# POWER_OSC_BOOT.net
KiCad netlist of a schematic drawn in Altium Designer
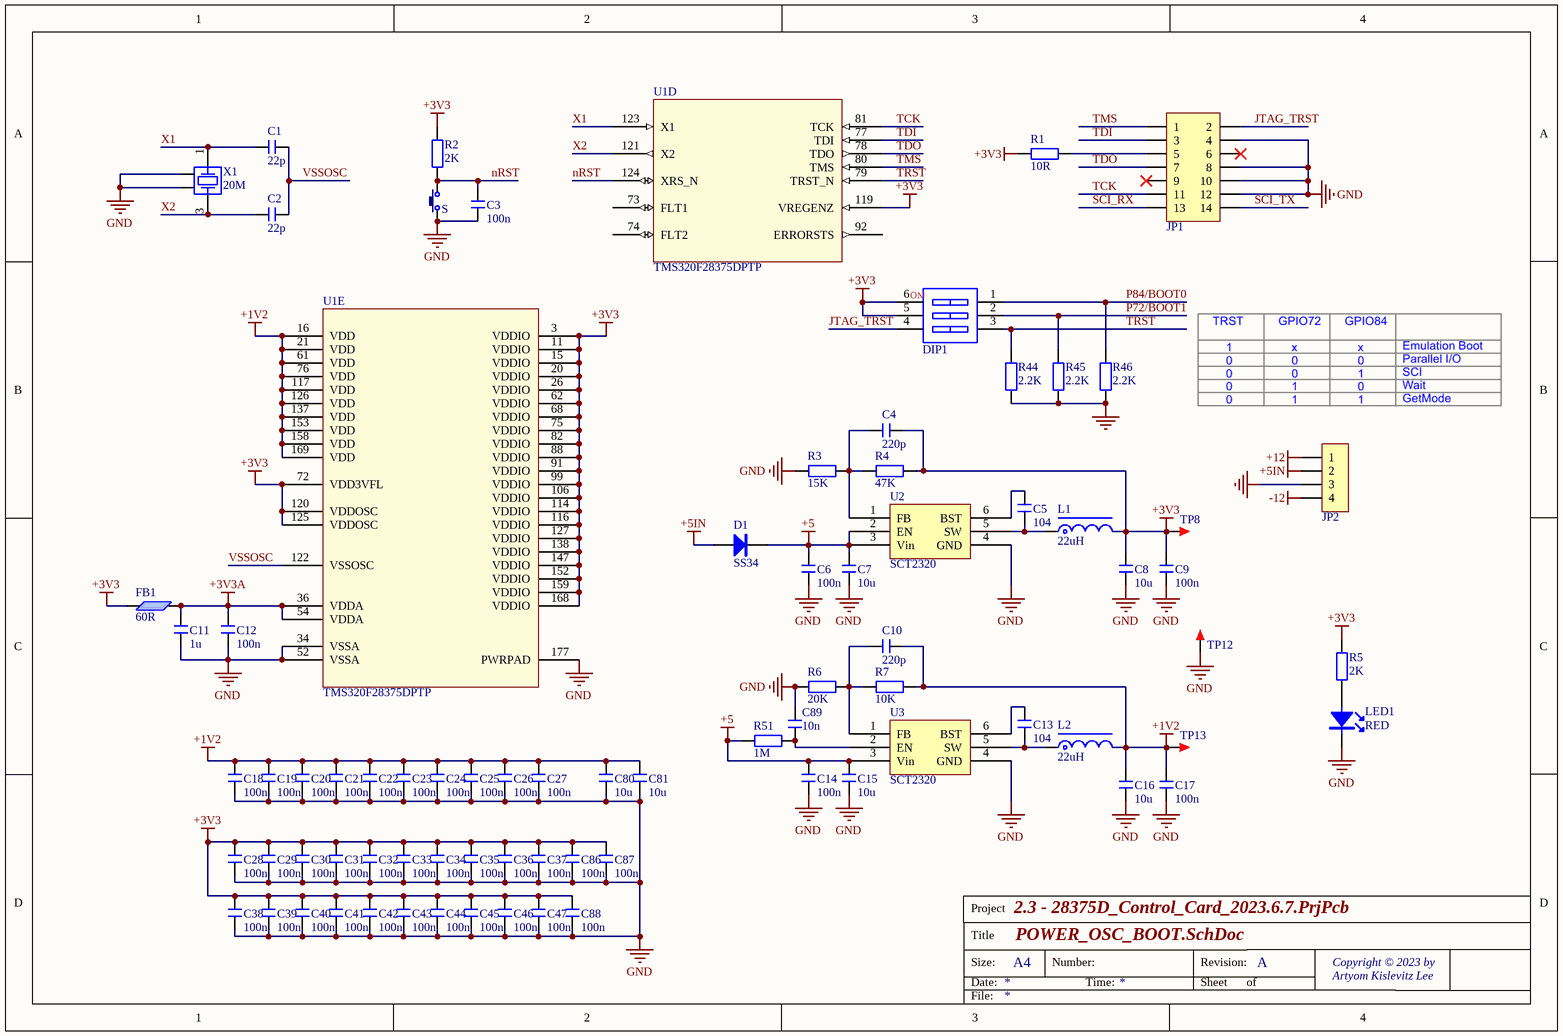
[diagram p0: POWER_OSC_BOOT.SchDoc]

(export (version "E")
  (design (tool "Eeschema 10.0.6"))
  (components
    (comp (ref "C1")
      (value "22p")
      (footprint "C 0805_L")
      (description "贴片电容")
      (libsource (lib "01 - 电容-电阻-电感") (part "C"))
    )
    (comp (ref "C2")
      (value "22p")
      (footprint "C 0805_L")
      (description "贴片电容")
      (libsource (lib "01 - 电容-电阻-电感") (part "C"))
    )
    (comp (ref "C3")
      (value "100n")
      (footprint "C 0805_L")
      (description "贴片电容")
      (libsource (lib "01 - 电容-电阻-电感") (part "C"))
    )
    (comp (ref "C4")
      (value "220p")
      (footprint "C 0805_L")
      (description "贴片电容")
      (libsource (lib "01 - 电容-电阻-电感") (part "C"))
    )
    (comp (ref "C5")
      (value "104")
      (footprint "C 0805_L")
      (description "贴片电容")
      (libsource (lib "01 - 电容-电阻-电感") (part "C"))
    )
    (comp (ref "C6")
      (value "100n")
      (footprint "C 0805_L")
      (description "贴片电容")
      (libsource (lib "01 - 电容-电阻-电感") (part "C"))
    )
    (comp (ref "C7")
      (value "10u")
      (footprint "C 1210_L")
      (description "贴片电容")
      (libsource (lib "01 - 电容-电阻-电感") (part "C"))
    )
    (comp (ref "C8")
      (value "10u")
      (footprint "C 1210_L")
      (description "贴片电容")
      (libsource (lib "01 - 电容-电阻-电感") (part "C"))
    )
    (comp (ref "C9")
      (value "100n")
      (footprint "C 0805_L")
      (description "贴片电容")
      (libsource (lib "01 - 电容-电阻-电感") (part "C"))
    )
    (comp (ref "C10")
      (value "220p")
      (footprint "C 0805_L")
      (description "贴片电容")
      (libsource (lib "01 - 电容-电阻-电感") (part "C"))
    )
    (comp (ref "C11")
      (value "1u")
      (footprint "C 0805_L")
      (description "贴片电容")
      (libsource (lib "01 - 电容-电阻-电感") (part "C"))
    )
    (comp (ref "C12")
      (value "100n")
      (footprint "C 0805_L")
      (description "贴片电容")
      (libsource (lib "01 - 电容-电阻-电感") (part "C"))
    )
    (comp (ref "C13")
      (value "104")
      (footprint "C 0805_L")
      (description "贴片电容")
      (libsource (lib "01 - 电容-电阻-电感") (part "C"))
    )
    (comp (ref "C14")
      (value "100n")
      (footprint "C 0805_L")
      (description "贴片电容")
      (libsource (lib "01 - 电容-电阻-电感") (part "C"))
    )
    (comp (ref "C15")
      (value "10u")
      (footprint "C 1210_L")
      (description "贴片电容")
      (libsource (lib "01 - 电容-电阻-电感") (part "C"))
    )
    (comp (ref "C16")
      (value "10u")
      (footprint "C 1210_L")
      (description "贴片电容")
      (libsource (lib "01 - 电容-电阻-电感") (part "C"))
    )
    (comp (ref "C17")
      (value "100n")
      (footprint "C 0805_L")
      (description "贴片电容")
      (libsource (lib "01 - 电容-电阻-电感") (part "C"))
    )
    (comp (ref "C18")
      (value "100n")
      (footprint "C 0603_L")
      (description "贴片电容")
      (libsource (lib "01 - 电容-电阻-电感") (part "C"))
    )
    (comp (ref "C19")
      (value "100n")
      (footprint "C 0603_L")
      (description "贴片电容")
      (libsource (lib "01 - 电容-电阻-电感") (part "C"))
    )
    (comp (ref "C20")
      (value "100n")
      (footprint "C 0603_L")
      (description "贴片电容")
      (libsource (lib "01 - 电容-电阻-电感") (part "C"))
    )
    (comp (ref "C21")
      (value "100n")
      (footprint "C 0603_L")
      (description "贴片电容")
      (libsource (lib "01 - 电容-电阻-电感") (part "C"))
    )
    (comp (ref "C22")
      (value "100n")
      (footprint "C 0603_L")
      (description "贴片电容")
      (libsource (lib "01 - 电容-电阻-电感") (part "C"))
    )
    (comp (ref "C23")
      (value "100n")
      (footprint "C 0603_L")
      (description "贴片电容")
      (libsource (lib "01 - 电容-电阻-电感") (part "C"))
    )
    (comp (ref "C24")
      (value "100n")
      (footprint "C 0603_L")
      (description "贴片电容")
      (libsource (lib "01 - 电容-电阻-电感") (part "C"))
    )
    (comp (ref "C25")
      (value "100n")
      (footprint "C 0603_L")
      (description "贴片电容")
      (libsource (lib "01 - 电容-电阻-电感") (part "C"))
    )
    (comp (ref "C26")
      (value "100n")
      (footprint "C 0603_L")
      (description "贴片电容")
      (libsource (lib "01 - 电容-电阻-电感") (part "C"))
    )
    (comp (ref "C27")
      (value "100n")
      (footprint "C 0603_L")
      (description "贴片电容")
      (libsource (lib "01 - 电容-电阻-电感") (part "C"))
    )
    (comp (ref "C28")
      (value "100n")
      (footprint "C 0603_L")
      (description "贴片电容")
      (libsource (lib "01 - 电容-电阻-电感") (part "C"))
    )
    (comp (ref "C29")
      (value "100n")
      (footprint "C 0603_L")
      (description "贴片电容")
      (libsource (lib "01 - 电容-电阻-电感") (part "C"))
    )
    (comp (ref "C30")
      (value "100n")
      (footprint "C 0603_L")
      (description "贴片电容")
      (libsource (lib "01 - 电容-电阻-电感") (part "C"))
    )
    (comp (ref "C31")
      (value "100n")
      (footprint "C 0603_L")
      (description "贴片电容")
      (libsource (lib "01 - 电容-电阻-电感") (part "C"))
    )
    (comp (ref "C32")
      (value "100n")
      (footprint "C 0603_L")
      (description "贴片电容")
      (libsource (lib "01 - 电容-电阻-电感") (part "C"))
    )
    (comp (ref "C33")
      (value "100n")
      (footprint "C 0603_L")
      (description "贴片电容")
      (libsource (lib "01 - 电容-电阻-电感") (part "C"))
    )
    (comp (ref "C34")
      (value "100n")
      (footprint "C 0603_L")
      (description "贴片电容")
      (libsource (lib "01 - 电容-电阻-电感") (part "C"))
    )
    (comp (ref "C35")
      (value "100n")
      (footprint "C 0603_L")
      (description "贴片电容")
      (libsource (lib "01 - 电容-电阻-电感") (part "C"))
    )
    (comp (ref "C36")
      (value "100n")
      (footprint "C 0603_L")
      (description "贴片电容")
      (libsource (lib "01 - 电容-电阻-电感") (part "C"))
    )
    (comp (ref "C37")
      (value "100n")
      (footprint "C 0603_L")
      (description "贴片电容")
      (libsource (lib "01 - 电容-电阻-电感") (part "C"))
    )
    (comp (ref "C38")
      (value "100n")
      (footprint "C 0603_L")
      (description "贴片电容")
      (libsource (lib "01 - 电容-电阻-电感") (part "C"))
    )
    (comp (ref "C39")
      (value "100n")
      (footprint "C 0603_L")
      (description "贴片电容")
      (libsource (lib "01 - 电容-电阻-电感") (part "C"))
    )
    (comp (ref "C40")
      (value "100n")
      (footprint "C 0603_L")
      (description "贴片电容")
      (libsource (lib "01 - 电容-电阻-电感") (part "C"))
    )
    (comp (ref "C41")
      (value "100n")
      (footprint "C 0603_L")
      (description "贴片电容")
      (libsource (lib "01 - 电容-电阻-电感") (part "C"))
    )
    (comp (ref "C42")
      (value "100n")
      (footprint "C 0603_L")
      (description "贴片电容")
      (libsource (lib "01 - 电容-电阻-电感") (part "C"))
    )
    (comp (ref "C43")
      (value "100n")
      (footprint "C 0603_L")
      (description "贴片电容")
      (libsource (lib "01 - 电容-电阻-电感") (part "C"))
    )
    (comp (ref "C44")
      (value "100n")
      (footprint "C 0603_L")
      (description "贴片电容")
      (libsource (lib "01 - 电容-电阻-电感") (part "C"))
    )
    (comp (ref "C45")
      (value "100n")
      (footprint "C 0603_L")
      (description "贴片电容")
      (libsource (lib "01 - 电容-电阻-电感") (part "C"))
    )
    (comp (ref "C46")
      (value "100n")
      (footprint "C 0603_L")
      (description "贴片电容")
      (libsource (lib "01 - 电容-电阻-电感") (part "C"))
    )
    (comp (ref "C47")
      (value "100n")
      (footprint "C 0603_L")
      (description "贴片电容")
      (libsource (lib "01 - 电容-电阻-电感") (part "C"))
    )
    (comp (ref "C80")
      (value "10u")
      (footprint "C 0805_L")
      (description "贴片电容")
      (libsource (lib "01 - 电容-电阻-电感") (part "C"))
    )
    (comp (ref "C81")
      (value "10u")
      (footprint "C 0805_L")
      (description "贴片电容")
      (libsource (lib "01 - 电容-电阻-电感") (part "C"))
    )
    (comp (ref "C86")
      (value "100n")
      (footprint "C 0603_L")
      (description "贴片电容")
      (libsource (lib "01 - 电容-电阻-电感") (part "C"))
    )
    (comp (ref "C87")
      (value "100n")
      (footprint "C 0603_L")
      (description "贴片电容")
      (libsource (lib "01 - 电容-电阻-电感") (part "C"))
    )
    (comp (ref "C88")
      (value "100n")
      (footprint "C 0603_L")
      (description "贴片电容")
      (libsource (lib "01 - 电容-电阻-电感") (part "C"))
    )
    (comp (ref "C89")
      (value "10n")
      (footprint "C 0805_L")
      (description "贴片电容")
      (libsource (lib "01 - 电容-电阻-电感") (part "C"))
    )
    (comp (ref "D1")
      (value "SS34")
      (footprint "SMA")
      (description "整流二极管")
      (libsource (lib "02 - 二极管(LED)-三极管-整流桥") (part "1N4007"))
    )
    (comp (ref "DIP1")
      (value "SW-3P")
      (footprint "CSW1.27 SMD-3P")
      (description "3路编码开关")
      (libsource (lib "03 - 按键-开关-晶振-蜂鸣器") (part "SW-3P"))
    )
    (comp (ref "FB1")
      (value "60R")
      (footprint "R 0805_L")
      (description "磁珠")
      (libsource (lib "01 - 电容-电阻-电感") (part "FB"))
    )
    (comp (ref "JP1")
      (value "Header 2X7")
      (footprint "IDC2.54-LI-2x7P")
      (description "7*2P接插件")
      (libsource (lib "18 - 接插件-脚距2.54mm (100mil) ") (part "Header 7X2"))
    )
    (comp (ref "JP2")
      (value "HDR-1X4")
      (footprint "KF2510-LI-4P")
      (description "4P接插件")
      (libsource (lib "18 - 接插件-脚距2.54mm (100mil) ") (part "Header 4"))
    )
    (comp (ref "L1")
      (value "22uH")
      (footprint "CDRH74")
      (description "功率屏蔽电感")
      (libsource (lib "01 - 电容-电阻-电感") (part "L-CDRH"))
    )
    (comp (ref "L2")
      (value "22uH")
      (footprint "CDRH74")
      (description "功率屏蔽电感")
      (libsource (lib "01 - 电容-电阻-电感") (part "L-CDRH"))
    )
    (comp (ref "LED1")
      (value "RED")
      (footprint "LED 0805R")
      (description "贴片LED")
      (libsource (lib "02 - 二极管(LED)-三极管-整流桥") (part "LED-SMD"))
    )
    (comp (ref "R1")
      (value "10R")
      (footprint "R 0805_L")
      (description "贴片电阻")
      (libsource (lib "01 - 电容-电阻-电感") (part "R"))
    )
    (comp (ref "R2")
      (value "2K")
      (footprint "R 0805_L")
      (description "贴片电阻")
      (libsource (lib "01 - 电容-电阻-电感") (part "R"))
    )
    (comp (ref "R3")
      (value "15K")
      (footprint "R 0805_L")
      (description "贴片电阻")
      (libsource (lib "01 - 电容-电阻-电感") (part "R"))
    )
    (comp (ref "R4")
      (value "47K")
      (footprint "R 0805_L")
      (description "贴片电阻")
      (libsource (lib "01 - 电容-电阻-电感") (part "R"))
    )
    (comp (ref "R5")
      (value "2K")
      (footprint "R 0805_L")
      (description "贴片电阻")
      (libsource (lib "01 - 电容-电阻-电感") (part "R"))
    )
    (comp (ref "R6")
      (value "20K")
      (footprint "R 0805_L")
      (description "贴片电阻")
      (libsource (lib "01 - 电容-电阻-电感") (part "R"))
    )
    (comp (ref "R7")
      (value "10K")
      (footprint "R 0805_L")
      (description "贴片电阻")
      (libsource (lib "01 - 电容-电阻-电感") (part "R"))
    )
    (comp (ref "R44")
      (value "2.2K")
      (footprint "R 0805_L")
      (description "贴片电阻")
      (libsource (lib "01 - 电容-电阻-电感") (part "R"))
    )
    (comp (ref "R45")
      (value "2.2K")
      (footprint "R 0805_L")
      (description "贴片电阻")
      (libsource (lib "01 - 电容-电阻-电感") (part "R"))
    )
    (comp (ref "R46")
      (value "2.2K")
      (footprint "R 0805_L")
      (description "贴片电阻")
      (libsource (lib "01 - 电容-电阻-电感") (part "R"))
    )
    (comp (ref "R51")
      (value "1M")
      (footprint "R 0805_L")
      (description "贴片电阻")
      (libsource (lib "01 - 电容-电阻-电感") (part "R"))
    )
    (comp (ref "S")
      (value "3x6x5")
      (footprint "TSW DIP-3*6*4.3")
      (description "3x6轻触开关")
      (libsource (lib "03 - 按键-开关-晶振-蜂鸣器") (part "TSW 3x6"))
    )
    (comp (ref "TP8")
      (value "TEST")
      (footprint "TEST 1.6")
      (description "测试点")
      (libsource (lib "10 - 未分类元器件") (part "TEST"))
    )
    (comp (ref "TP12")
      (value "TEST")
      (footprint "TEST 1.6")
      (description "测试点")
      (libsource (lib "10 - 未分类元器件") (part "TEST"))
    )
    (comp (ref "TP13")
      (value "TEST")
      (footprint "TEST 1.6")
      (description "测试点")
      (libsource (lib "10 - 未分类元器件") (part "TEST"))
    )
    (comp (ref "U1")
      (value "TMS320F28375DPTP")
      (footprint "LQFP176-E 24x24_N")
      (description "DSP 176")
      (fields
        (field (name "PARTNUMBER") "TMS320F28377DPTP")
        (field (name "MANUFACTURER") "Texas Instruments")
      )
      (libsource (lib "39 - 其他芯片类") (part "TMS320F28377DPTP"))
    )
    (comp (ref "U2") (value "SCT2320") (footprint "SOT23-6") (libsource (lib "Schlib1") (part "SCT2330")))
    (comp (ref "U3") (value "SCT2320") (footprint "SOT23-6") (libsource (lib "Schlib1") (part "SCT2330")))
    (comp (ref "X1")
      (value "20M")
      (footprint "OSC 3225-4P")
      (description "4脚无源晶振")
      (libsource (lib "03 - 按键-开关-晶振-蜂鸣器") (part "XTAL-4P"))
    )
  )
  (nets
    (net (code "1") (name "+1V2") (class "Default")
      (node (ref "C10") (pin "2") (pinfunction "2_2") (pintype "passive"))
      (node (ref "C16") (pin "2") (pinfunction "2_2") (pintype "passive"))
      (node (ref "C17") (pin "2") (pinfunction "2_2") (pintype "passive"))
      (node (ref "C18") (pin "2") (pinfunction "2_2") (pintype "passive"))
      (node (ref "C19") (pin "2") (pinfunction "2_2") (pintype "passive"))
      (node (ref "C20") (pin "2") (pinfunction "2_2") (pintype "passive"))
      (node (ref "C21") (pin "2") (pinfunction "2_2") (pintype "passive"))
      (node (ref "C22") (pin "2") (pinfunction "2_2") (pintype "passive"))
      (node (ref "C23") (pin "2") (pinfunction "2_2") (pintype "passive"))
      (node (ref "C24") (pin "2") (pinfunction "2_2") (pintype "passive"))
      (node (ref "C25") (pin "2") (pinfunction "2_2") (pintype "passive"))
      (node (ref "C26") (pin "2") (pinfunction "2_2") (pintype "passive"))
      (node (ref "C27") (pin "2") (pinfunction "2_2") (pintype "passive"))
      (node (ref "C80") (pin "2") (pinfunction "2_2") (pintype "passive"))
      (node (ref "C81") (pin "2") (pinfunction "2_2") (pintype "passive"))
      (node (ref "L2") (pin "2") (pinfunction "2_2") (pintype "passive"))
      (node (ref "R7") (pin "2") (pinfunction "2_2") (pintype "passive"))
      (node (ref "TP13") (pin "1") (pinfunction "1_1") (pintype "passive"))
      (node (ref "U1") (pin "117") (pinfunction "VDD_117") (pintype "power_in"))
      (node (ref "U1") (pin "126") (pinfunction "VDD_126") (pintype "power_in"))
      (node (ref "U1") (pin "137") (pinfunction "VDD_137") (pintype "power_in"))
      (node (ref "U1") (pin "153") (pinfunction "VDD_153") (pintype "power_in"))
      (node (ref "U1") (pin "158") (pinfunction "VDD_158") (pintype "power_in"))
      (node (ref "U1") (pin "16") (pinfunction "VDD_16") (pintype "power_in"))
      (node (ref "U1") (pin "169") (pinfunction "VDD_169") (pintype "power_in"))
      (node (ref "U1") (pin "21") (pinfunction "VDD_21") (pintype "power_in"))
      (node (ref "U1") (pin "61") (pinfunction "VDD_61") (pintype "power_in"))
      (node (ref "U1") (pin "76") (pinfunction "VDD_76") (pintype "power_in"))
    )
    (net (code "2") (name "+3V3") (class "Default")
      (node (ref "C28") (pin "2") (pinfunction "2_2") (pintype "passive"))
      (node (ref "C29") (pin "2") (pinfunction "2_2") (pintype "passive"))
      (node (ref "C30") (pin "2") (pinfunction "2_2") (pintype "passive"))
      (node (ref "C31") (pin "2") (pinfunction "2_2") (pintype "passive"))
      (node (ref "C32") (pin "2") (pinfunction "2_2") (pintype "passive"))
      (node (ref "C33") (pin "2") (pinfunction "2_2") (pintype "passive"))
      (node (ref "C34") (pin "2") (pinfunction "2_2") (pintype "passive"))
      (node (ref "C35") (pin "2") (pinfunction "2_2") (pintype "passive"))
      (node (ref "C36") (pin "2") (pinfunction "2_2") (pintype "passive"))
      (node (ref "C37") (pin "2") (pinfunction "2_2") (pintype "passive"))
      (node (ref "C38") (pin "2") (pinfunction "2_2") (pintype "passive"))
      (node (ref "C39") (pin "2") (pinfunction "2_2") (pintype "passive"))
      (node (ref "C4") (pin "2") (pinfunction "2_2") (pintype "passive"))
      (node (ref "C40") (pin "2") (pinfunction "2_2") (pintype "passive"))
      (node (ref "C41") (pin "2") (pinfunction "2_2") (pintype "passive"))
      (node (ref "C42") (pin "2") (pinfunction "2_2") (pintype "passive"))
      (node (ref "C43") (pin "2") (pinfunction "2_2") (pintype "passive"))
      (node (ref "C44") (pin "2") (pinfunction "2_2") (pintype "passive"))
      (node (ref "C45") (pin "2") (pinfunction "2_2") (pintype "passive"))
      (node (ref "C46") (pin "2") (pinfunction "2_2") (pintype "passive"))
      (node (ref "C47") (pin "2") (pinfunction "2_2") (pintype "passive"))
      (node (ref "C8") (pin "2") (pinfunction "2_2") (pintype "passive"))
      (node (ref "C86") (pin "2") (pinfunction "2_2") (pintype "passive"))
      (node (ref "C87") (pin "2") (pinfunction "2_2") (pintype "passive"))
      (node (ref "C88") (pin "2") (pinfunction "2_2") (pintype "passive"))
      (node (ref "C9") (pin "2") (pinfunction "2_2") (pintype "passive"))
      (node (ref "DIP1") (pin "5") (pinfunction "5_5") (pintype "passive"))
      (node (ref "DIP1") (pin "6") (pinfunction "6_6") (pintype "passive"))
      (node (ref "FB1") (pin "1") (pinfunction "1_1") (pintype "passive"))
      (node (ref "L1") (pin "2") (pinfunction "2_2") (pintype "passive"))
      (node (ref "R1") (pin "2") (pinfunction "2_2") (pintype "passive"))
      (node (ref "R2") (pin "2") (pinfunction "2_2") (pintype "passive"))
      (node (ref "R4") (pin "2") (pinfunction "2_2") (pintype "passive"))
      (node (ref "R5") (pin "2") (pinfunction "2_2") (pintype "passive"))
      (node (ref "TP8") (pin "1") (pinfunction "1_1") (pintype "passive"))
      (node (ref "U1") (pin "106") (pinfunction "VDDIO_106") (pintype "power_in"))
      (node (ref "U1") (pin "11") (pinfunction "VDDIO_11") (pintype "power_in"))
      (node (ref "U1") (pin "114") (pinfunction "VDDIO_114") (pintype "power_in"))
      (node (ref "U1") (pin "116") (pinfunction "VDDIO_116") (pintype "power_in"))
      (node (ref "U1") (pin "119") (pinfunction "VREGENZ_119") (pintype "input"))
      (node (ref "U1") (pin "120") (pinfunction "VDDOSC_120") (pintype "power_in"))
      (node (ref "U1") (pin "125") (pinfunction "VDDOSC_125") (pintype "power_in"))
      (node (ref "U1") (pin "127") (pinfunction "VDDIO_127") (pintype "power_in"))
      (node (ref "U1") (pin "138") (pinfunction "VDDIO_138") (pintype "power_in"))
      (node (ref "U1") (pin "147") (pinfunction "VDDIO_147") (pintype "power_in"))
      (node (ref "U1") (pin "15") (pinfunction "VDDIO_15") (pintype "power_in"))
      (node (ref "U1") (pin "152") (pinfunction "VDDIO_152") (pintype "power_in"))
      (node (ref "U1") (pin "159") (pinfunction "VDDIO_159") (pintype "power_in"))
      (node (ref "U1") (pin "168") (pinfunction "VDDIO_168") (pintype "power_in"))
      (node (ref "U1") (pin "20") (pinfunction "VDDIO_20") (pintype "power_in"))
      (node (ref "U1") (pin "26") (pinfunction "VDDIO_26") (pintype "power_in"))
      (node (ref "U1") (pin "3") (pinfunction "VDDIO_3") (pintype "power_in"))
      (node (ref "U1") (pin "62") (pinfunction "VDDIO_62") (pintype "power_in"))
      (node (ref "U1") (pin "68") (pinfunction "VDDIO_68") (pintype "power_in"))
      (node (ref "U1") (pin "72") (pinfunction "VDD3VFL_72") (pintype "power_in"))
      (node (ref "U1") (pin "75") (pinfunction "VDDIO_75") (pintype "power_in"))
      (node (ref "U1") (pin "82") (pinfunction "VDDIO_82") (pintype "power_in"))
      (node (ref "U1") (pin "88") (pinfunction "VDDIO_88") (pintype "power_in"))
      (node (ref "U1") (pin "91") (pinfunction "VDDIO_91") (pintype "power_in"))
      (node (ref "U1") (pin "99") (pinfunction "VDDIO_99") (pintype "power_in"))
    )
    (net (code "3") (name "+3V3A") (class "Default")
      (node (ref "C11") (pin "2") (pinfunction "2_2") (pintype "passive"))
      (node (ref "C12") (pin "2") (pinfunction "2_2") (pintype "passive"))
      (node (ref "FB1") (pin "2") (pinfunction "2_2") (pintype "passive"))
      (node (ref "U1") (pin "36") (pinfunction "VDDA_36") (pintype "power_in"))
      (node (ref "U1") (pin "54") (pinfunction "VDDA_54") (pintype "power_in"))
    )
    (net (code "4") (name "+5") (class "Default")
      (node (ref "C14") (pin "2") (pinfunction "2_2") (pintype "passive"))
      (node (ref "C15") (pin "2") (pinfunction "2_2") (pintype "passive"))
      (node (ref "C6") (pin "2") (pinfunction "2_2") (pintype "passive"))
      (node (ref "C7") (pin "2") (pinfunction "2_2") (pintype "passive"))
      (node (ref "D1") (pin "2") (pinfunction "K_2") (pintype "passive"))
      (node (ref "R51") (pin "1") (pinfunction "1_1") (pintype "passive"))
      (node (ref "U2") (pin "2") (pinfunction "EN_2") (pintype "passive"))
      (node (ref "U2") (pin "3") (pinfunction "Vin_3") (pintype "passive"))
      (node (ref "U3") (pin "3") (pinfunction "Vin_3") (pintype "passive"))
    )
    (net (code "5") (name "+5IN") (class "Default")
      (node (ref "D1") (pin "1") (pinfunction "A_1") (pintype "passive"))
      (node (ref "JP2") (pin "2") (pinfunction "2_2") (pintype "passive"))
    )
    (net (code "6") (name "+12") (class "Default")
      (node (ref "JP2") (pin "1") (pinfunction "1_1") (pintype "passive"))
    )
    (net (code "7") (name "-12") (class "Default")
      (node (ref "JP2") (pin "4") (pinfunction "4_4") (pintype "passive"))
    )
    (net (code "8") (name "/JTAG_TRST") (class "Default")
      (node (ref "DIP1") (pin "4") (pinfunction "4_4") (pintype "passive"))
      (node (ref "JP1") (pin "2") (pinfunction "2_2") (pintype "passive"))
    )
    (net (code "9") (name "/P72{slash}BOOT1") (class "Default")
      (node (ref "DIP1") (pin "2") (pinfunction "2_2") (pintype "passive"))
      (node (ref "R45") (pin "1") (pinfunction "1_1") (pintype "passive"))
    )
    (net (code "10") (name "/P84{slash}BOOT0") (class "Default")
      (node (ref "DIP1") (pin "1") (pinfunction "1_1") (pintype "passive"))
      (node (ref "R46") (pin "1") (pinfunction "1_1") (pintype "passive"))
    )
    (net (code "11") (name "/SCI_RX") (class "Default")
      (node (ref "JP1") (pin "13") (pinfunction "13_13") (pintype "passive"))
    )
    (net (code "12") (name "/SCI_TX") (class "Default")
      (node (ref "JP1") (pin "14") (pinfunction "14_14") (pintype "passive"))
    )
    (net (code "13") (name "/TCK") (class "Default")
      (node (ref "JP1") (pin "11") (pinfunction "11_11") (pintype "passive"))
      (node (ref "U1") (pin "81") (pinfunction "TCK_81") (pintype "input"))
    )
    (net (code "14") (name "/TDI") (class "Default")
      (node (ref "JP1") (pin "3") (pinfunction "3_3") (pintype "passive"))
      (node (ref "U1") (pin "77") (pinfunction "TDI_77") (pintype "input"))
    )
    (net (code "15") (name "/TDO") (class "Default")
      (node (ref "JP1") (pin "7") (pinfunction "7_7") (pintype "passive"))
      (node (ref "U1") (pin "78") (pinfunction "TDO_78") (pintype "output"))
    )
    (net (code "16") (name "/TMS") (class "Default")
      (node (ref "JP1") (pin "1") (pinfunction "1_1") (pintype "passive"))
      (node (ref "U1") (pin "80") (pinfunction "TMS_80") (pintype "input"))
    )
    (net (code "17") (name "/TRST") (class "Default")
      (node (ref "DIP1") (pin "3") (pinfunction "3_3") (pintype "passive"))
      (node (ref "R44") (pin "1") (pinfunction "1_1") (pintype "passive"))
      (node (ref "U1") (pin "79") (pinfunction "TRST_N_79") (pintype "input"))
    )
    (net (code "18") (name "/VSSOSC") (class "Default")
      (node (ref "C1") (pin "1") (pinfunction "1_1") (pintype "passive"))
      (node (ref "C2") (pin "1") (pinfunction "1_1") (pintype "passive"))
      (node (ref "U1") (pin "122") (pinfunction "VSSOSC_122") (pintype "power_in"))
    )
    (net (code "19") (name "/X1") (class "Default")
      (node (ref "C1") (pin "2") (pinfunction "2_2") (pintype "passive"))
      (node (ref "U1") (pin "123") (pinfunction "X1_123") (pintype "input"))
      (node (ref "X1") (pin "1") (pinfunction "1_1") (pintype "passive"))
    )
    (net (code "20") (name "/X2") (class "Default")
      (node (ref "C2") (pin "2") (pinfunction "2_2") (pintype "passive"))
      (node (ref "U1") (pin "121") (pinfunction "X2_121") (pintype "output"))
      (node (ref "X1") (pin "3") (pinfunction "3_3") (pintype "passive"))
    )
    (net (code "21") (name "/nRST") (class "Default")
      (node (ref "C3") (pin "2") (pinfunction "2_2") (pintype "passive"))
      (node (ref "R2") (pin "1") (pinfunction "1_1") (pintype "passive"))
      (node (ref "S") (pin "2") (pinfunction "2_2") (pintype "passive"))
      (node (ref "U1") (pin "124") (pinfunction "XRS_N_124") (pintype "bidirectional"))
    )
    (net (code "22") (name "GND") (class "Default")
      (node (ref "C11") (pin "1") (pinfunction "1_1") (pintype "passive"))
      (node (ref "C12") (pin "1") (pinfunction "1_1") (pintype "passive"))
      (node (ref "C14") (pin "1") (pinfunction "1_1") (pintype "passive"))
      (node (ref "C15") (pin "1") (pinfunction "1_1") (pintype "passive"))
      (node (ref "C16") (pin "1") (pinfunction "1_1") (pintype "passive"))
      (node (ref "C17") (pin "1") (pinfunction "1_1") (pintype "passive"))
      (node (ref "C18") (pin "1") (pinfunction "1_1") (pintype "passive"))
      (node (ref "C19") (pin "1") (pinfunction "1_1") (pintype "passive"))
      (node (ref "C20") (pin "1") (pinfunction "1_1") (pintype "passive"))
      (node (ref "C21") (pin "1") (pinfunction "1_1") (pintype "passive"))
      (node (ref "C22") (pin "1") (pinfunction "1_1") (pintype "passive"))
      (node (ref "C23") (pin "1") (pinfunction "1_1") (pintype "passive"))
      (node (ref "C24") (pin "1") (pinfunction "1_1") (pintype "passive"))
      (node (ref "C25") (pin "1") (pinfunction "1_1") (pintype "passive"))
      (node (ref "C26") (pin "1") (pinfunction "1_1") (pintype "passive"))
      (node (ref "C27") (pin "1") (pinfunction "1_1") (pintype "passive"))
      (node (ref "C28") (pin "1") (pinfunction "1_1") (pintype "passive"))
      (node (ref "C29") (pin "1") (pinfunction "1_1") (pintype "passive"))
      (node (ref "C3") (pin "1") (pinfunction "1_1") (pintype "passive"))
      (node (ref "C30") (pin "1") (pinfunction "1_1") (pintype "passive"))
      (node (ref "C31") (pin "1") (pinfunction "1_1") (pintype "passive"))
      (node (ref "C32") (pin "1") (pinfunction "1_1") (pintype "passive"))
      (node (ref "C33") (pin "1") (pinfunction "1_1") (pintype "passive"))
      (node (ref "C34") (pin "1") (pinfunction "1_1") (pintype "passive"))
      (node (ref "C35") (pin "1") (pinfunction "1_1") (pintype "passive"))
      (node (ref "C36") (pin "1") (pinfunction "1_1") (pintype "passive"))
      (node (ref "C37") (pin "1") (pinfunction "1_1") (pintype "passive"))
      (node (ref "C38") (pin "1") (pinfunction "1_1") (pintype "passive"))
      (node (ref "C39") (pin "1") (pinfunction "1_1") (pintype "passive"))
      (node (ref "C40") (pin "1") (pinfunction "1_1") (pintype "passive"))
      (node (ref "C41") (pin "1") (pinfunction "1_1") (pintype "passive"))
      (node (ref "C42") (pin "1") (pinfunction "1_1") (pintype "passive"))
      (node (ref "C43") (pin "1") (pinfunction "1_1") (pintype "passive"))
      (node (ref "C44") (pin "1") (pinfunction "1_1") (pintype "passive"))
      (node (ref "C45") (pin "1") (pinfunction "1_1") (pintype "passive"))
      (node (ref "C46") (pin "1") (pinfunction "1_1") (pintype "passive"))
      (node (ref "C47") (pin "1") (pinfunction "1_1") (pintype "passive"))
      (node (ref "C6") (pin "1") (pinfunction "1_1") (pintype "passive"))
      (node (ref "C7") (pin "1") (pinfunction "1_1") (pintype "passive"))
      (node (ref "C8") (pin "1") (pinfunction "1_1") (pintype "passive"))
      (node (ref "C80") (pin "1") (pinfunction "1_1") (pintype "passive"))
      (node (ref "C81") (pin "1") (pinfunction "1_1") (pintype "passive"))
      (node (ref "C86") (pin "1") (pinfunction "1_1") (pintype "passive"))
      (node (ref "C87") (pin "1") (pinfunction "1_1") (pintype "passive"))
      (node (ref "C88") (pin "1") (pinfunction "1_1") (pintype "passive"))
      (node (ref "C89") (pin "2") (pinfunction "2_2") (pintype "passive"))
      (node (ref "C9") (pin "1") (pinfunction "1_1") (pintype "passive"))
      (node (ref "JP1") (pin "10") (pinfunction "10_10") (pintype "passive"))
      (node (ref "JP1") (pin "12") (pinfunction "12_12") (pintype "passive"))
      (node (ref "JP1") (pin "4") (pinfunction "4_4") (pintype "passive"))
      (node (ref "JP1") (pin "8") (pinfunction "8_8") (pintype "passive"))
      (node (ref "JP2") (pin "3") (pinfunction "3_3") (pintype "passive"))
      (node (ref "LED1") (pin "2") (pinfunction "K_2") (pintype "passive"))
      (node (ref "R3") (pin "1") (pinfunction "1_1") (pintype "passive"))
      (node (ref "R44") (pin "2") (pinfunction "2_2") (pintype "passive"))
      (node (ref "R45") (pin "2") (pinfunction "2_2") (pintype "passive"))
      (node (ref "R46") (pin "2") (pinfunction "2_2") (pintype "passive"))
      (node (ref "R6") (pin "1") (pinfunction "1_1") (pintype "passive"))
      (node (ref "S") (pin "1") (pinfunction "1_1") (pintype "passive"))
      (node (ref "TP12") (pin "1") (pinfunction "1_1") (pintype "passive"))
      (node (ref "U1") (pin "177") (pinfunction "PWRPAD_177") (pintype "power_in"))
      (node (ref "U1") (pin "34") (pinfunction "VSSA_34") (pintype "power_in"))
      (node (ref "U1") (pin "52") (pinfunction "VSSA_52") (pintype "power_in"))
      (node (ref "U2") (pin "4") (pinfunction "GND_4") (pintype "passive"))
      (node (ref "U3") (pin "4") (pinfunction "GND_4") (pintype "passive"))
      (node (ref "X1") (pin "2") (pinfunction "2_2") (pintype "passive"))
      (node (ref "X1") (pin "4") (pinfunction "4_4") (pintype "passive"))
    )
    (net (code "23") (name "Net-(JP1-Pad5)") (class "Default")
      (node (ref "JP1") (pin "5") (pinfunction "5_5") (pintype "passive"))
      (node (ref "R1") (pin "1") (pinfunction "1_1") (pintype "passive"))
    )
    (net (code "24") (name "Net-(LED1-A)") (class "Default")
      (node (ref "LED1") (pin "1") (pinfunction "A_1") (pintype "passive"))
      (node (ref "R5") (pin "1") (pinfunction "1_1") (pintype "passive"))
    )
    (net (code "25") (name "Net-(U2-BST)") (class "Default")
      (node (ref "C5") (pin "1") (pinfunction "1_1") (pintype "passive"))
      (node (ref "U2") (pin "6") (pinfunction "BST_6") (pintype "passive"))
    )
    (net (code "26") (name "Net-(U2-FB)") (class "Default")
      (node (ref "C4") (pin "1") (pinfunction "1_1") (pintype "passive"))
      (node (ref "R3") (pin "2") (pinfunction "2_2") (pintype "passive"))
      (node (ref "R4") (pin "1") (pinfunction "1_1") (pintype "passive"))
      (node (ref "U2") (pin "1") (pinfunction "FB_1") (pintype "passive"))
    )
    (net (code "27") (name "Net-(U2-SW)") (class "Default")
      (node (ref "C5") (pin "2") (pinfunction "2_2") (pintype "passive"))
      (node (ref "L1") (pin "1") (pinfunction "1_1") (pintype "passive"))
      (node (ref "U2") (pin "5") (pinfunction "SW_5") (pintype "passive"))
    )
    (net (code "28") (name "Net-(U3-BST)") (class "Default")
      (node (ref "C13") (pin "1") (pinfunction "1_1") (pintype "passive"))
      (node (ref "U3") (pin "6") (pinfunction "BST_6") (pintype "passive"))
    )
    (net (code "29") (name "Net-(U3-EN)") (class "Default")
      (node (ref "C89") (pin "1") (pinfunction "1_1") (pintype "passive"))
      (node (ref "R51") (pin "2") (pinfunction "2_2") (pintype "passive"))
      (node (ref "U3") (pin "2") (pinfunction "EN_2") (pintype "passive"))
    )
    (net (code "30") (name "Net-(U3-FB)") (class "Default")
      (node (ref "C10") (pin "1") (pinfunction "1_1") (pintype "passive"))
      (node (ref "R6") (pin "2") (pinfunction "2_2") (pintype "passive"))
      (node (ref "R7") (pin "1") (pinfunction "1_1") (pintype "passive"))
      (node (ref "U3") (pin "1") (pinfunction "FB_1") (pintype "passive"))
    )
    (net (code "31") (name "Net-(U3-SW)") (class "Default")
      (node (ref "C13") (pin "2") (pinfunction "2_2") (pintype "passive"))
      (node (ref "L2") (pin "1") (pinfunction "1_1") (pintype "passive"))
      (node (ref "U3") (pin "5") (pinfunction "SW_5") (pintype "passive"))
    )
    (net (code "32") (name "unconnected-(JP1-Pad6)") (class "Default")
      (node (ref "JP1") (pin "6") (pinfunction "6_6") (pintype "passive+no_connect"))
    )
    (net (code "33") (name "unconnected-(JP1-Pad9)") (class "Default")
      (node (ref "JP1") (pin "9") (pinfunction "9_9") (pintype "passive+no_connect"))
    )
    (net (code "34") (name "unconnected-(U1D-ERRORSTS-Pad92)") (class "Default")
      (node (ref "U1") (pin "92") (pinfunction "ERRORSTS_92") (pintype "output"))
    )
    (net (code "35") (name "unconnected-(U1D-FLT1-Pad73)") (class "Default")
      (node (ref "U1") (pin "73") (pinfunction "FLT1_73") (pintype "bidirectional"))
    )
    (net (code "36") (name "unconnected-(U1D-FLT2-Pad74)") (class "Default")
      (node (ref "U1") (pin "74") (pinfunction "FLT2_74") (pintype "bidirectional"))
    )
  )
)
